# mainboard.net
KiCad netlist of a schematic drawn in Altium Designer
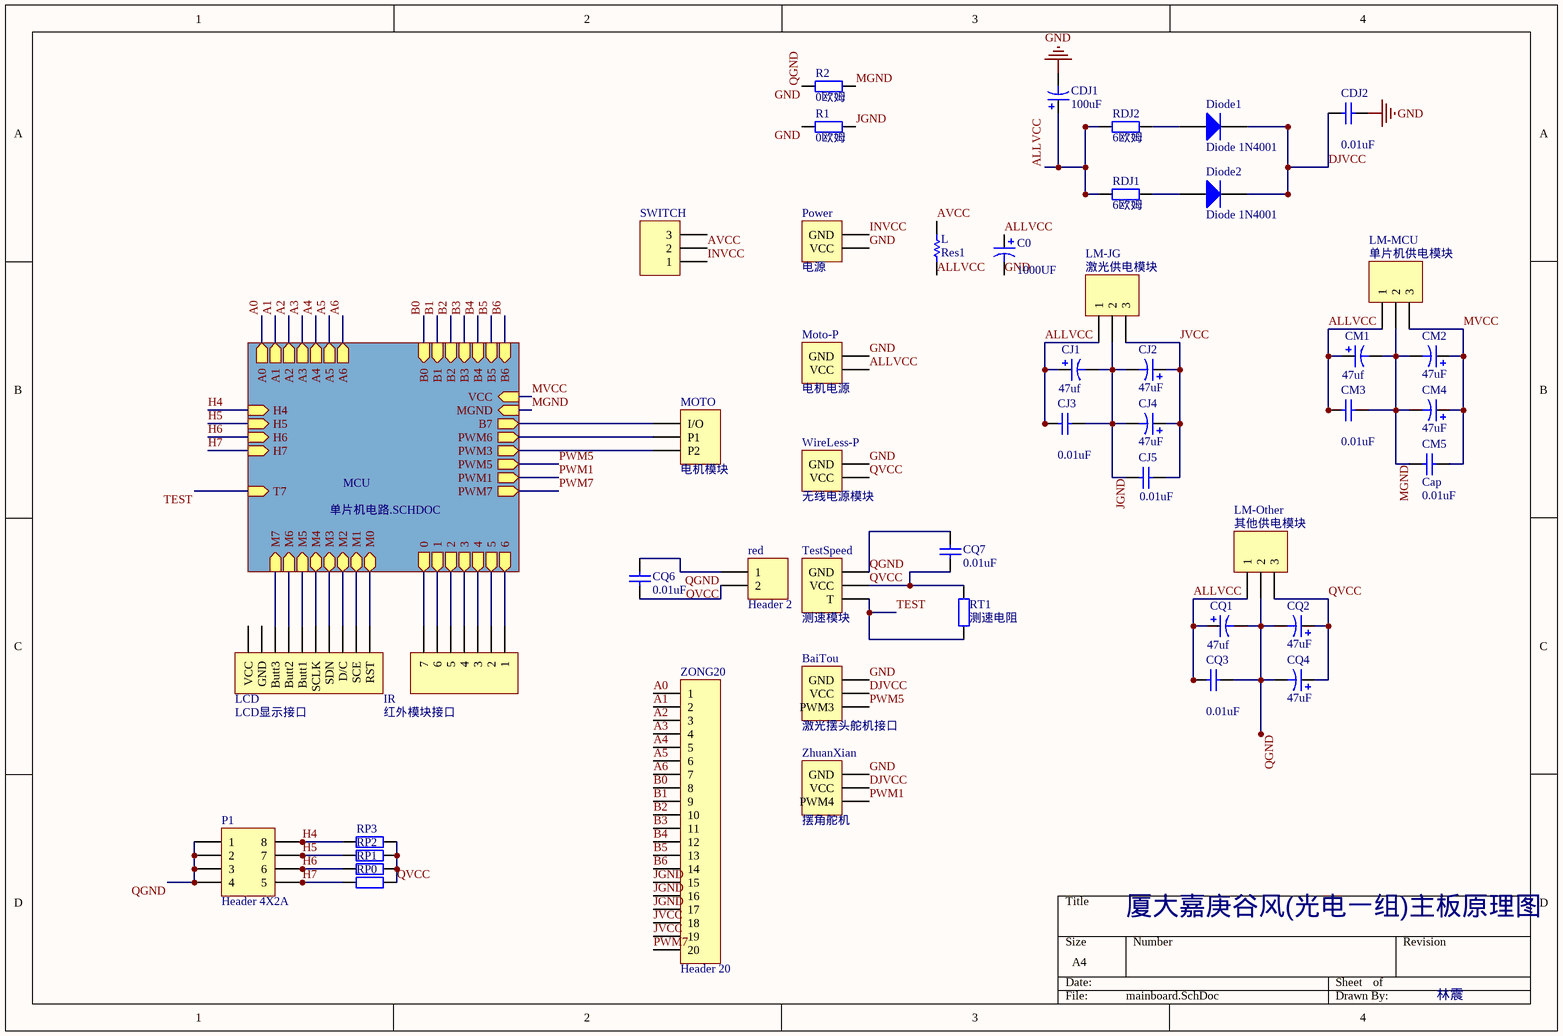
[diagram p0: mainboard.SchDoc]

(export (version "E")
  (design (tool "Eeschema 10.0.6"))
  (components
    (comp (ref "BaiTou")
      (value "激光摆头舵机接口")
      (footprint "HDR1X3")
      (description "Header, 3-Pin")
      (fields (field (name "PUBLISHER") "Altium Limited"))
      (libsource (lib "Miscellaneous Connectors") (part "Header 3"))
    )
    (comp (ref "C0")
      (value "1000UF")
      (footprint "1000UF")
      (description "Polarized Capacitor (Surface Mount)")
      (fields (field (name "Comment") "BATT") (field (name "PUBLISHER") "Altium Limited"))
      (libsource (lib "Miscellaneous Devices") (part "Cap Pol3"))
    )
    (comp (ref "CDJ1")
      (value "100uF")
      (footprint "100UF")
      (description "Polarized Capacitor (Radial)")
      (fields (field (name "PUBLISHER") "Altium Limited"))
      (libsource (lib "Miscellaneous Devices") (part "Cap Pol1"))
    )
    (comp (ref "CDJ2")
      (value "0.01uF")
      (footprint "mainLib:0805")
      (description "Capacitor")
      (fields (field (name "Comment") "Cap") (field (name "PUBLISHER") "Altium Limited"))
      (libsource (lib "Miscellaneous Devices") (part "Cap"))
    )
    (comp (ref "CJ1")
      (value "47uf")
      (footprint "mainLib:3528")
      (description "Polarized Capacitor (Surface Mount)")
      (fields (field (name "Comment") "Cap Pol3") (field (name "PUBLISHER") "Altium Limited"))
      (libsource (lib "Miscellaneous Devices") (part "Cap Pol3"))
    )
    (comp (ref "CJ2")
      (value "47uF")
      (footprint "mainLib:3528")
      (description "Polarized Capacitor (Radial)")
      (fields (field (name "PUBLISHER") "Altium Limited"))
      (libsource (lib "Miscellaneous Devices") (part "Cap Pol1"))
    )
    (comp (ref "CJ3")
      (value "0.01uF")
      (footprint "mainLib:0805")
      (description "Capacitor")
      (fields (field (name "Comment") "Cap") (field (name "PUBLISHER") "Altium Limited"))
      (libsource (lib "Miscellaneous Devices") (part "Cap"))
    )
    (comp (ref "CJ4")
      (value "47uF")
      (footprint "mainLib:47UF")
      (description "Polarized Capacitor (Radial)")
      (fields (field (name "PUBLISHER") "Altium Limited"))
      (libsource (lib "Miscellaneous Devices") (part "Cap Pol1"))
    )
    (comp (ref "CJ5")
      (value "0.01uF")
      (footprint "mainLib:0805")
      (description "Capacitor")
      (fields (field (name "Comment") "Cap") (field (name "PUBLISHER") "Altium Limited"))
      (libsource (lib "Miscellaneous Devices") (part "Cap"))
    )
    (comp (ref "CM1")
      (value "47uf")
      (footprint "mainLib:3528")
      (description "Polarized Capacitor (Surface Mount)")
      (fields (field (name "Comment") "Cap Pol3") (field (name "PUBLISHER") "Altium Limited"))
      (libsource (lib "Miscellaneous Devices") (part "Cap Pol3"))
    )
    (comp (ref "CM2")
      (value "47uF")
      (footprint "mainLib:3528")
      (description "Polarized Capacitor (Radial)")
      (fields (field (name "PUBLISHER") "Altium Limited"))
      (libsource (lib "Miscellaneous Devices") (part "Cap Pol1"))
    )
    (comp (ref "CM3")
      (value "0.01uF")
      (footprint "mainLib:0805")
      (description "Capacitor")
      (fields (field (name "Comment") "Cap") (field (name "PUBLISHER") "Altium Limited"))
      (libsource (lib "Miscellaneous Devices") (part "Cap"))
    )
    (comp (ref "CM4")
      (value "47uF")
      (footprint "mainLib:47UF")
      (description "Polarized Capacitor (Radial)")
      (fields (field (name "PUBLISHER") "Altium Limited"))
      (libsource (lib "Miscellaneous Devices") (part "Cap Pol1"))
    )
    (comp (ref "CM5")
      (value "Cap")
      (footprint "mainLib:0805")
      (description "Capacitor")
      (fields (field (name "ALTIUM_VALUE") "0.01uF") (field (name "PUBLISHER") "Altium Limited"))
      (libsource (lib "Miscellaneous Devices") (part "Cap"))
    )
    (comp (ref "CQ1")
      (value "47uf")
      (footprint "mainLib:3528")
      (description "Polarized Capacitor (Surface Mount)")
      (fields (field (name "Comment") "Cap Pol3") (field (name "PUBLISHER") "Altium Limited"))
      (libsource (lib "Miscellaneous Devices") (part "Cap Pol3"))
    )
    (comp (ref "CQ2")
      (value "47uF")
      (footprint "mainLib:3528")
      (description "Polarized Capacitor (Radial)")
      (fields (field (name "PUBLISHER") "Altium Limited"))
      (libsource (lib "Miscellaneous Devices") (part "Cap Pol1"))
    )
    (comp (ref "CQ3")
      (value "0.01uF")
      (footprint "mainLib:0805")
      (description "Capacitor")
      (fields (field (name "Comment") "Cap") (field (name "PUBLISHER") "Altium Limited"))
      (libsource (lib "Miscellaneous Devices") (part "Cap"))
    )
    (comp (ref "CQ4")
      (value "47uF")
      (footprint "mainLib:47UF")
      (description "Polarized Capacitor (Radial)")
      (fields (field (name "PUBLISHER") "Altium Limited"))
      (libsource (lib "Miscellaneous Devices") (part "Cap Pol1"))
    )
    (comp (ref "CQ6")
      (value "0.01uF")
      (footprint "mainLib:0805")
      (description "Capacitor")
      (fields (field (name "Comment") "Cap") (field (name "PUBLISHER") "Altium Limited"))
      (libsource (lib "Miscellaneous Devices") (part "Cap"))
    )
    (comp (ref "CQ7")
      (value "0.01uF")
      (footprint "mainLib:0805")
      (description "Capacitor")
      (fields (field (name "Comment") "Cap") (field (name "PUBLISHER") "Altium Limited"))
      (libsource (lib "Miscellaneous Devices") (part "Cap"))
    )
    (comp (ref "Diode1")
      (value "Diode 1N4001")
      (footprint "DO-41")
      (description "1 Amp General Purpose Rectifier")
      (fields (field (name "PUBLISHER") "Altium Limited"))
      (libsource (lib "Miscellaneous Devices") (part "Diode 1N4001"))
    )
    (comp (ref "Diode2")
      (value "Diode 1N4001")
      (footprint "DO-41")
      (description "1 Amp General Purpose Rectifier")
      (fields (field (name "PUBLISHER") "Altium Limited"))
      (libsource (lib "Miscellaneous Devices") (part "Diode 1N4001"))
    )
    (comp (ref "IR")
      (value "红外模块接口")
      (footprint "HDR1X7")
      (description "Header, 7-Pin")
      (fields (field (name "PUBLISHER") "Altium Limited"))
      (libsource (lib "Miscellaneous Connectors") (part "Header 7"))
    )
    (comp (ref "L")
      (value "Res1")
      (footprint "10UH")
      (description "Resistor")
      (fields (field (name "PUBLISHER") "Altium Limited"))
      (libsource (lib "Miscellaneous Devices") (part "Res1"))
    )
    (comp (ref "LCD")
      (value "LCD显示接口")
      (footprint "HDR1X10")
      (description "Header, 10-Pin")
      (fields (field (name "PUBLISHER") "Altium Limited"))
      (libsource (lib "Miscellaneous Connectors") (part "Header 10"))
    )
    (comp (ref "LM-JG")
      (value "激光供电模块")
      (footprint "HDR1X3")
      (description "Header, 3-Pin")
      (fields (field (name "PUBLISHER") "Altium Limited"))
      (libsource (lib "") (part "Header 3_1"))
    )
    (comp (ref "LM-MCU")
      (value "单片机供电模块")
      (footprint "HDR1X3")
      (description "Header, 3-Pin")
      (fields (field (name "PUBLISHER") "Altium Limited"))
      (libsource (lib "") (part "Header 3_1"))
    )
    (comp (ref "LM-Other")
      (value "其他供电模块")
      (footprint "HDR1X3")
      (description "Header, 3-Pin")
      (fields (field (name "PUBLISHER") "Altium Limited"))
      (libsource (lib "") (part "Header 3_1"))
    )
    (comp (ref "MOTO")
      (value "电机模块")
      (footprint "HDR1X3")
      (description "Header, 3-Pin")
      (fields (field (name "PUBLISHER") "Altium Limited"))
      (libsource (lib "") (part "Header 3_2"))
    )
    (comp (ref "Moto-P")
      (value "电机电源")
      (footprint "tongzhu")
      (description "Header, 2-Pin")
      (fields (field (name "PUBLISHER") "Altium Limited"))
      (libsource (lib "Miscellaneous Connectors") (part "Header 2"))
    )
    (comp (ref "P1")
      (value "Header 4X2A")
      (footprint "DIP8")
      (description "Header, 4-Pin, Dual row")
      (fields (field (name "PUBLISHER") "Altium Limited"))
      (libsource (lib "Miscellaneous Connectors") (part "Header 4X2A"))
    )
    (comp (ref "Power")
      (value "电源")
      (footprint "tongzhu")
      (description "Header, 2-Pin")
      (fields (field (name "PUBLISHER") "Altium Limited"))
      (libsource (lib "Miscellaneous Connectors") (part "Header 2"))
    )
    (comp (ref "R1")
      (value "0欧姆")
      (footprint "0805")
      (description "Resistor")
      (fields (field (name "PUBLISHER") "Altium Limited"))
      (libsource (lib "Miscellaneous Devices") (part "Res2"))
    )
    (comp (ref "R2")
      (value "0欧姆")
      (footprint "0805")
      (description "Resistor")
      (fields (field (name "PUBLISHER") "Altium Limited"))
      (libsource (lib "Miscellaneous Devices") (part "Res2"))
    )
    (comp (ref "RDJ1")
      (value "6欧姆")
      (footprint "0805")
      (description "Resistor")
      (fields (field (name "PUBLISHER") "Altium Limited"))
      (libsource (lib "Miscellaneous Devices") (part "Res2"))
    )
    (comp (ref "RDJ2")
      (value "6欧姆")
      (footprint "0805")
      (description "Resistor")
      (fields (field (name "PUBLISHER") "Altium Limited"))
      (libsource (lib "Miscellaneous Devices") (part "Res2"))
    )
    (comp (ref "red")
      (value "Header 2")
      (footprint "HDR1X2")
      (description "Header, 2-Pin")
      (fields (field (name "PUBLISHER") "Altium Limited"))
      (libsource (lib "") (part "Header 2_1"))
    )
    (comp (ref "RP0")
      (value "Res2")
      (footprint "0805")
      (description "Resistor")
      (fields (field (name "PUBLISHER") "Altium Limited"))
      (libsource (lib "Miscellaneous Devices") (part "Res2"))
    )
    (comp (ref "RP1")
      (value "Res2")
      (footprint "0805")
      (description "Resistor")
      (fields (field (name "PUBLISHER") "Altium Limited"))
      (libsource (lib "Miscellaneous Devices") (part "Res2"))
    )
    (comp (ref "RP2")
      (value "Res2")
      (footprint "0805")
      (description "Resistor")
      (fields (field (name "PUBLISHER") "Altium Limited"))
      (libsource (lib "Miscellaneous Devices") (part "Res2"))
    )
    (comp (ref "RP3")
      (value "Res2")
      (footprint "0805")
      (description "Resistor")
      (fields (field (name "PUBLISHER") "Altium Limited"))
      (libsource (lib "Miscellaneous Devices") (part "Res2"))
    )
    (comp (ref "RT1")
      (value "测速电阻")
      (footprint "0805")
      (description "Resistor")
      (fields (field (name "PUBLISHER") "Altium Limited"))
      (libsource (lib "") (part "Res2_1"))
    )
    (comp (ref "SWITCH")
      (value "SWITCH")
      (footprint "SWITCH")
      (description "Header, 3-Pin")
      (fields (field (name "PUBLISHER") "Altium Limited"))
      (libsource (lib "") (part "Header 3_5"))
    )
    (comp (ref "TestSpeed")
      (value "测速模块")
      (footprint "HDR1X3")
      (description "Header, 3-Pin")
      (fields (field (name "PUBLISHER") "Altium Limited"))
      (libsource (lib "") (part "Header 3_4"))
    )
    (comp (ref "WireLess-P")
      (value "无线电源模块")
      (footprint "HDR1X2")
      (description "Header, 2-Pin")
      (fields (field (name "PUBLISHER") "Altium Limited"))
      (libsource (lib "Miscellaneous Connectors") (part "Header 2"))
    )
    (comp (ref "ZhuanXian")
      (value "摆角舵机")
      (footprint "HDR1X3")
      (description "Header, 3-Pin")
      (fields (field (name "PUBLISHER") "Altium Limited"))
      (libsource (lib "") (part "Header 3_3"))
    )
    (comp (ref "ZONG20")
      (value "Header 20")
      (footprint "ZONG20")
      (description "传感下来引脚")
      (fields (field (name "PUBLISHER") "Altium Limited"))
      (libsource (lib "Miscellaneous Connectors") (part "Header 20"))
    )
  )
  (nets
    (net (code "1") (name "/0") (class "Default")
      (node (ref "IR") (pin "7") (pinfunction "7_7") (pintype "passive"))
    )
    (net (code "2") (name "/1") (class "Default")
      (node (ref "IR") (pin "6") (pinfunction "6_6") (pintype "passive"))
    )
    (net (code "3") (name "/2") (class "Default")
      (node (ref "IR") (pin "5") (pinfunction "5_5") (pintype "passive"))
    )
    (net (code "4") (name "/3") (class "Default")
      (node (ref "IR") (pin "4") (pinfunction "4_4") (pintype "passive"))
    )
    (net (code "5") (name "/4") (class "Default")
      (node (ref "IR") (pin "3") (pinfunction "3_3") (pintype "passive"))
    )
    (net (code "6") (name "/5") (class "Default")
      (node (ref "IR") (pin "2") (pinfunction "2_2") (pintype "passive"))
    )
    (net (code "7") (name "/6") (class "Default")
      (node (ref "IR") (pin "1") (pinfunction "1_1") (pintype "passive"))
    )
    (net (code "8") (name "/A0") (class "Default")
      (node (ref "ZONG20") (pin "1") (pinfunction "1_1") (pintype "passive"))
    )
    (net (code "9") (name "/A1") (class "Default")
      (node (ref "ZONG20") (pin "2") (pinfunction "2_2") (pintype "passive"))
    )
    (net (code "10") (name "/A2") (class "Default")
      (node (ref "ZONG20") (pin "3") (pinfunction "3_3") (pintype "passive"))
    )
    (net (code "11") (name "/A3") (class "Default")
      (node (ref "ZONG20") (pin "4") (pinfunction "4_4") (pintype "passive"))
    )
    (net (code "12") (name "/A4") (class "Default")
      (node (ref "ZONG20") (pin "5") (pinfunction "5_5") (pintype "passive"))
    )
    (net (code "13") (name "/A5") (class "Default")
      (node (ref "ZONG20") (pin "6") (pinfunction "6_6") (pintype "passive"))
    )
    (net (code "14") (name "/A6") (class "Default")
      (node (ref "ZONG20") (pin "7") (pinfunction "7_7") (pintype "passive"))
    )
    (net (code "15") (name "/ALLVCC") (class "Default")
      (node (ref "C0") (pin "1") (pinfunction "1_1") (pintype "passive"))
      (node (ref "CDJ1") (pin "1") (pinfunction "1_1") (pintype "passive"))
      (node (ref "CJ1") (pin "1") (pinfunction "1_1") (pintype "passive"))
      (node (ref "CJ3") (pin "2") (pinfunction "2_2") (pintype "passive"))
      (node (ref "CM1") (pin "1") (pinfunction "1_1") (pintype "passive"))
      (node (ref "CM3") (pin "2") (pinfunction "2_2") (pintype "passive"))
      (node (ref "CQ1") (pin "1") (pinfunction "1_1") (pintype "passive"))
      (node (ref "CQ3") (pin "2") (pinfunction "2_2") (pintype "passive"))
      (node (ref "L") (pin "1") (pinfunction "1_1") (pintype "passive"))
      (node (ref "LM-JG") (pin "1") (pinfunction "1_1") (pintype "passive"))
      (node (ref "LM-MCU") (pin "1") (pinfunction "1_1") (pintype "passive"))
      (node (ref "LM-Other") (pin "1") (pinfunction "1_1") (pintype "passive"))
      (node (ref "Moto-P") (pin "1") (pinfunction "VCC_1") (pintype "passive"))
      (node (ref "RDJ1") (pin "2") (pinfunction "2_2") (pintype "passive"))
      (node (ref "RDJ2") (pin "2") (pinfunction "2_2") (pintype "passive"))
    )
    (net (code "16") (name "/AVCC") (class "Default")
      (node (ref "L") (pin "2") (pinfunction "2_2") (pintype "passive"))
      (node (ref "SWITCH") (pin "2") (pinfunction "2_2") (pintype "passive"))
    )
    (net (code "17") (name "/B0") (class "Default")
      (node (ref "ZONG20") (pin "8") (pinfunction "8_8") (pintype "passive"))
    )
    (net (code "18") (name "/B1") (class "Default")
      (node (ref "ZONG20") (pin "9") (pinfunction "9_9") (pintype "passive"))
    )
    (net (code "19") (name "/B2") (class "Default")
      (node (ref "ZONG20") (pin "10") (pinfunction "10_10") (pintype "passive"))
    )
    (net (code "20") (name "/B3") (class "Default")
      (node (ref "ZONG20") (pin "11") (pinfunction "11_11") (pintype "passive"))
    )
    (net (code "21") (name "/B4") (class "Default")
      (node (ref "ZONG20") (pin "12") (pinfunction "12_12") (pintype "passive"))
    )
    (net (code "22") (name "/B5") (class "Default")
      (node (ref "ZONG20") (pin "13") (pinfunction "13_13") (pintype "passive"))
    )
    (net (code "23") (name "/B6") (class "Default")
      (node (ref "ZONG20") (pin "14") (pinfunction "14_14") (pintype "passive"))
    )
    (net (code "24") (name "/B7") (class "Default")
      (node (ref "MOTO") (pin "2") (pinfunction "I/O_2") (pintype "passive"))
    )
    (net (code "25") (name "/DJVCC") (class "Default")
      (node (ref "BaiTou") (pin "2") (pinfunction "VCC_2") (pintype "passive"))
      (node (ref "CDJ2") (pin "2") (pinfunction "2_2") (pintype "passive"))
      (node (ref "Diode1") (pin "2") (pinfunction "K_2") (pintype "passive"))
      (node (ref "Diode2") (pin "2") (pinfunction "K_2") (pintype "passive"))
      (node (ref "ZhuanXian") (pin "2") (pinfunction "VCC_2") (pintype "passive"))
    )
    (net (code "26") (name "/H4") (class "Default")
      (node (ref "P1") (pin "5") (pinfunction "8_5") (pintype "passive"))
      (node (ref "RP3") (pin "2") (pinfunction "2_2") (pintype "passive"))
    )
    (net (code "27") (name "/H5") (class "Default")
      (node (ref "P1") (pin "6") (pinfunction "7_6") (pintype "passive"))
      (node (ref "RP2") (pin "2") (pinfunction "2_2") (pintype "passive"))
    )
    (net (code "28") (name "/H6") (class "Default")
      (node (ref "P1") (pin "7") (pinfunction "6_7") (pintype "passive"))
      (node (ref "RP1") (pin "2") (pinfunction "2_2") (pintype "passive"))
    )
    (net (code "29") (name "/H7") (class "Default")
      (node (ref "P1") (pin "8") (pinfunction "5_8") (pintype "passive"))
      (node (ref "RP0") (pin "2") (pinfunction "2_2") (pintype "passive"))
    )
    (net (code "30") (name "/INVCC") (class "Default")
      (node (ref "Power") (pin "2") (pinfunction "GND_2") (pintype "passive"))
      (node (ref "SWITCH") (pin "1") (pinfunction "1_1") (pintype "passive"))
    )
    (net (code "31") (name "/JGND") (class "Default")
      (node (ref "CJ1") (pin "2") (pinfunction "2_2") (pintype "passive"))
      (node (ref "CJ2") (pin "2") (pinfunction "2_2") (pintype "passive"))
      (node (ref "CJ3") (pin "1") (pinfunction "1_1") (pintype "passive"))
      (node (ref "CJ4") (pin "2") (pinfunction "2_2") (pintype "passive"))
      (node (ref "CJ5") (pin "2") (pinfunction "2_2") (pintype "passive"))
      (node (ref "LM-JG") (pin "2") (pinfunction "2_2") (pintype "passive"))
      (node (ref "R1") (pin "1") (pinfunction "1_1") (pintype "passive"))
      (node (ref "ZONG20") (pin "15") (pinfunction "15_15") (pintype "passive"))
      (node (ref "ZONG20") (pin "16") (pinfunction "16_16") (pintype "passive"))
      (node (ref "ZONG20") (pin "17") (pinfunction "17_17") (pintype "passive"))
    )
    (net (code "32") (name "/JVCC") (class "Default")
      (node (ref "CJ2") (pin "1") (pinfunction "1_1") (pintype "passive"))
      (node (ref "CJ4") (pin "1") (pinfunction "1_1") (pintype "passive"))
      (node (ref "CJ5") (pin "1") (pinfunction "1_1") (pintype "passive"))
      (node (ref "LM-JG") (pin "3") (pinfunction "3_3") (pintype "passive"))
      (node (ref "ZONG20") (pin "18") (pinfunction "18_18") (pintype "passive"))
      (node (ref "ZONG20") (pin "19") (pinfunction "19_19") (pintype "passive"))
    )
    (net (code "33") (name "/M0") (class "Default")
      (node (ref "LCD") (pin "1") (pinfunction "RST_1") (pintype "passive"))
    )
    (net (code "34") (name "/M1") (class "Default")
      (node (ref "LCD") (pin "2") (pinfunction "SCE_2") (pintype "passive"))
    )
    (net (code "35") (name "/M2") (class "Default")
      (node (ref "LCD") (pin "3") (pinfunction "D/C_3") (pintype "passive"))
    )
    (net (code "36") (name "/M3") (class "Default")
      (node (ref "LCD") (pin "4") (pinfunction "SDN_4") (pintype "passive"))
    )
    (net (code "37") (name "/M4") (class "Default")
      (node (ref "LCD") (pin "5") (pinfunction "SCLK_5") (pintype "passive"))
    )
    (net (code "38") (name "/M5") (class "Default")
      (node (ref "LCD") (pin "6") (pinfunction "Butt1_6") (pintype "passive"))
    )
    (net (code "39") (name "/M6") (class "Default")
      (node (ref "LCD") (pin "7") (pinfunction "Butt2_7") (pintype "passive"))
    )
    (net (code "40") (name "/M7") (class "Default")
      (node (ref "LCD") (pin "8") (pinfunction "Butt3_8") (pintype "passive"))
    )
    (net (code "41") (name "/MGND") (class "Default")
      (node (ref "CM1") (pin "2") (pinfunction "2_2") (pintype "passive"))
      (node (ref "CM2") (pin "2") (pinfunction "2_2") (pintype "passive"))
      (node (ref "CM3") (pin "1") (pinfunction "1_1") (pintype "passive"))
      (node (ref "CM4") (pin "2") (pinfunction "2_2") (pintype "passive"))
      (node (ref "CM5") (pin "2") (pinfunction "2_2") (pintype "passive"))
      (node (ref "LM-MCU") (pin "2") (pinfunction "2_2") (pintype "passive"))
      (node (ref "R2") (pin "1") (pinfunction "1_1") (pintype "passive"))
    )
    (net (code "42") (name "/MVCC") (class "Default")
      (node (ref "CM2") (pin "1") (pinfunction "1_1") (pintype "passive"))
      (node (ref "CM4") (pin "1") (pinfunction "1_1") (pintype "passive"))
      (node (ref "CM5") (pin "1") (pinfunction "1_1") (pintype "passive"))
      (node (ref "LM-MCU") (pin "3") (pinfunction "3_3") (pintype "passive"))
    )
    (net (code "43") (name "/PWM1") (class "Default")
      (node (ref "ZhuanXian") (pin "1") (pinfunction "PWM4_1") (pintype "passive"))
    )
    (net (code "44") (name "/PWM3") (class "Default")
      (node (ref "MOTO") (pin "3") (pinfunction "P2_3") (pintype "passive"))
    )
    (net (code "45") (name "/PWM5") (class "Default")
      (node (ref "BaiTou") (pin "1") (pinfunction "PWM3_1") (pintype "passive"))
    )
    (net (code "46") (name "/PWM6") (class "Default")
      (node (ref "MOTO") (pin "1") (pinfunction "P1_1") (pintype "passive"))
    )
    (net (code "47") (name "/PWM7") (class "Default")
      (node (ref "ZONG20") (pin "20") (pinfunction "20_20") (pintype "passive"))
    )
    (net (code "48") (name "/QVCC") (class "Default")
      (node (ref "CQ2") (pin "1") (pinfunction "1_1") (pintype "passive"))
      (node (ref "CQ4") (pin "1") (pinfunction "1_1") (pintype "passive"))
      (node (ref "CQ6") (pin "2") (pinfunction "2_2") (pintype "passive"))
      (node (ref "CQ7") (pin "2") (pinfunction "2_2") (pintype "passive"))
      (node (ref "LM-Other") (pin "3") (pinfunction "3_3") (pintype "passive"))
      (node (ref "RP0") (pin "1") (pinfunction "1_1") (pintype "passive"))
      (node (ref "RP1") (pin "1") (pinfunction "1_1") (pintype "passive"))
      (node (ref "RP2") (pin "1") (pinfunction "1_1") (pintype "passive"))
      (node (ref "RP3") (pin "1") (pinfunction "1_1") (pintype "passive"))
      (node (ref "RT1") (pin "1") (pinfunction "1_1") (pintype "passive"))
      (node (ref "TestSpeed") (pin "2") (pinfunction "VCC_2") (pintype "passive"))
      (node (ref "WireLess-P") (pin "1") (pinfunction "VCC_1") (pintype "passive"))
      (node (ref "red") (pin "2") (pinfunction "2_2") (pintype "passive"))
    )
    (net (code "49") (name "/TEST") (class "Default")
      (node (ref "RT1") (pin "2") (pinfunction "2_2") (pintype "passive"))
      (node (ref "TestSpeed") (pin "1") (pinfunction "T_1") (pintype "passive"))
    )
    (net (code "50") (name "GND") (class "Default")
      (node (ref "BaiTou") (pin "3") (pinfunction "GND_3") (pintype "passive"))
      (node (ref "C0") (pin "2") (pinfunction "2_2") (pintype "passive"))
      (node (ref "CDJ1") (pin "2") (pinfunction "2_2") (pintype "passive"))
      (node (ref "CDJ2") (pin "1") (pinfunction "1_1") (pintype "passive"))
      (node (ref "CQ1") (pin "2") (pinfunction "2_2") (pintype "passive"))
      (node (ref "CQ2") (pin "2") (pinfunction "2_2") (pintype "passive"))
      (node (ref "CQ3") (pin "1") (pinfunction "1_1") (pintype "passive"))
      (node (ref "CQ4") (pin "2") (pinfunction "2_2") (pintype "passive"))
      (node (ref "CQ6") (pin "1") (pinfunction "1_1") (pintype "passive"))
      (node (ref "CQ7") (pin "1") (pinfunction "1_1") (pintype "passive"))
      (node (ref "LM-Other") (pin "2") (pinfunction "2_2") (pintype "passive"))
      (node (ref "Moto-P") (pin "2") (pinfunction "GND_2") (pintype "passive"))
      (node (ref "P1") (pin "1") (pinfunction "1_1") (pintype "passive"))
      (node (ref "P1") (pin "2") (pinfunction "2_2") (pintype "passive"))
      (node (ref "P1") (pin "3") (pinfunction "3_3") (pintype "passive"))
      (node (ref "P1") (pin "4") (pinfunction "4_4") (pintype "passive"))
      (node (ref "Power") (pin "1") (pinfunction "VCC_1") (pintype "passive"))
      (node (ref "R1") (pin "2") (pinfunction "2_2") (pintype "passive"))
      (node (ref "R2") (pin "2") (pinfunction "2_2") (pintype "passive"))
      (node (ref "TestSpeed") (pin "3") (pinfunction "GND_3") (pintype "passive"))
      (node (ref "WireLess-P") (pin "2") (pinfunction "GND_2") (pintype "passive"))
      (node (ref "ZhuanXian") (pin "3") (pinfunction "GND_3") (pintype "passive"))
      (node (ref "red") (pin "1") (pinfunction "1_1") (pintype "passive"))
    )
    (net (code "51") (name "Net-(Diode1-A)") (class "Default")
      (node (ref "Diode1") (pin "1") (pinfunction "A_1") (pintype "passive"))
      (node (ref "RDJ2") (pin "1") (pinfunction "1_1") (pintype "passive"))
    )
    (net (code "52") (name "Net-(Diode2-A)") (class "Default")
      (node (ref "Diode2") (pin "1") (pinfunction "A_1") (pintype "passive"))
      (node (ref "RDJ1") (pin "1") (pinfunction "1_1") (pintype "passive"))
    )
    (net (code "53") (name "unconnected-(LCD-GND-Pad9)") (class "Default")
      (node (ref "LCD") (pin "9") (pinfunction "GND_9") (pintype "passive"))
    )
    (net (code "54") (name "unconnected-(LCD-VCC-Pad10)") (class "Default")
      (node (ref "LCD") (pin "10") (pinfunction "VCC_10") (pintype "passive"))
    )
    (net (code "55") (name "unconnected-(SWITCH-Pad3)") (class "Default")
      (node (ref "SWITCH") (pin "3") (pinfunction "3_3") (pintype "passive"))
    )
  )
)
